# tick-mk-2.net
KiCad netlist of a schematic drawn in EAGLE
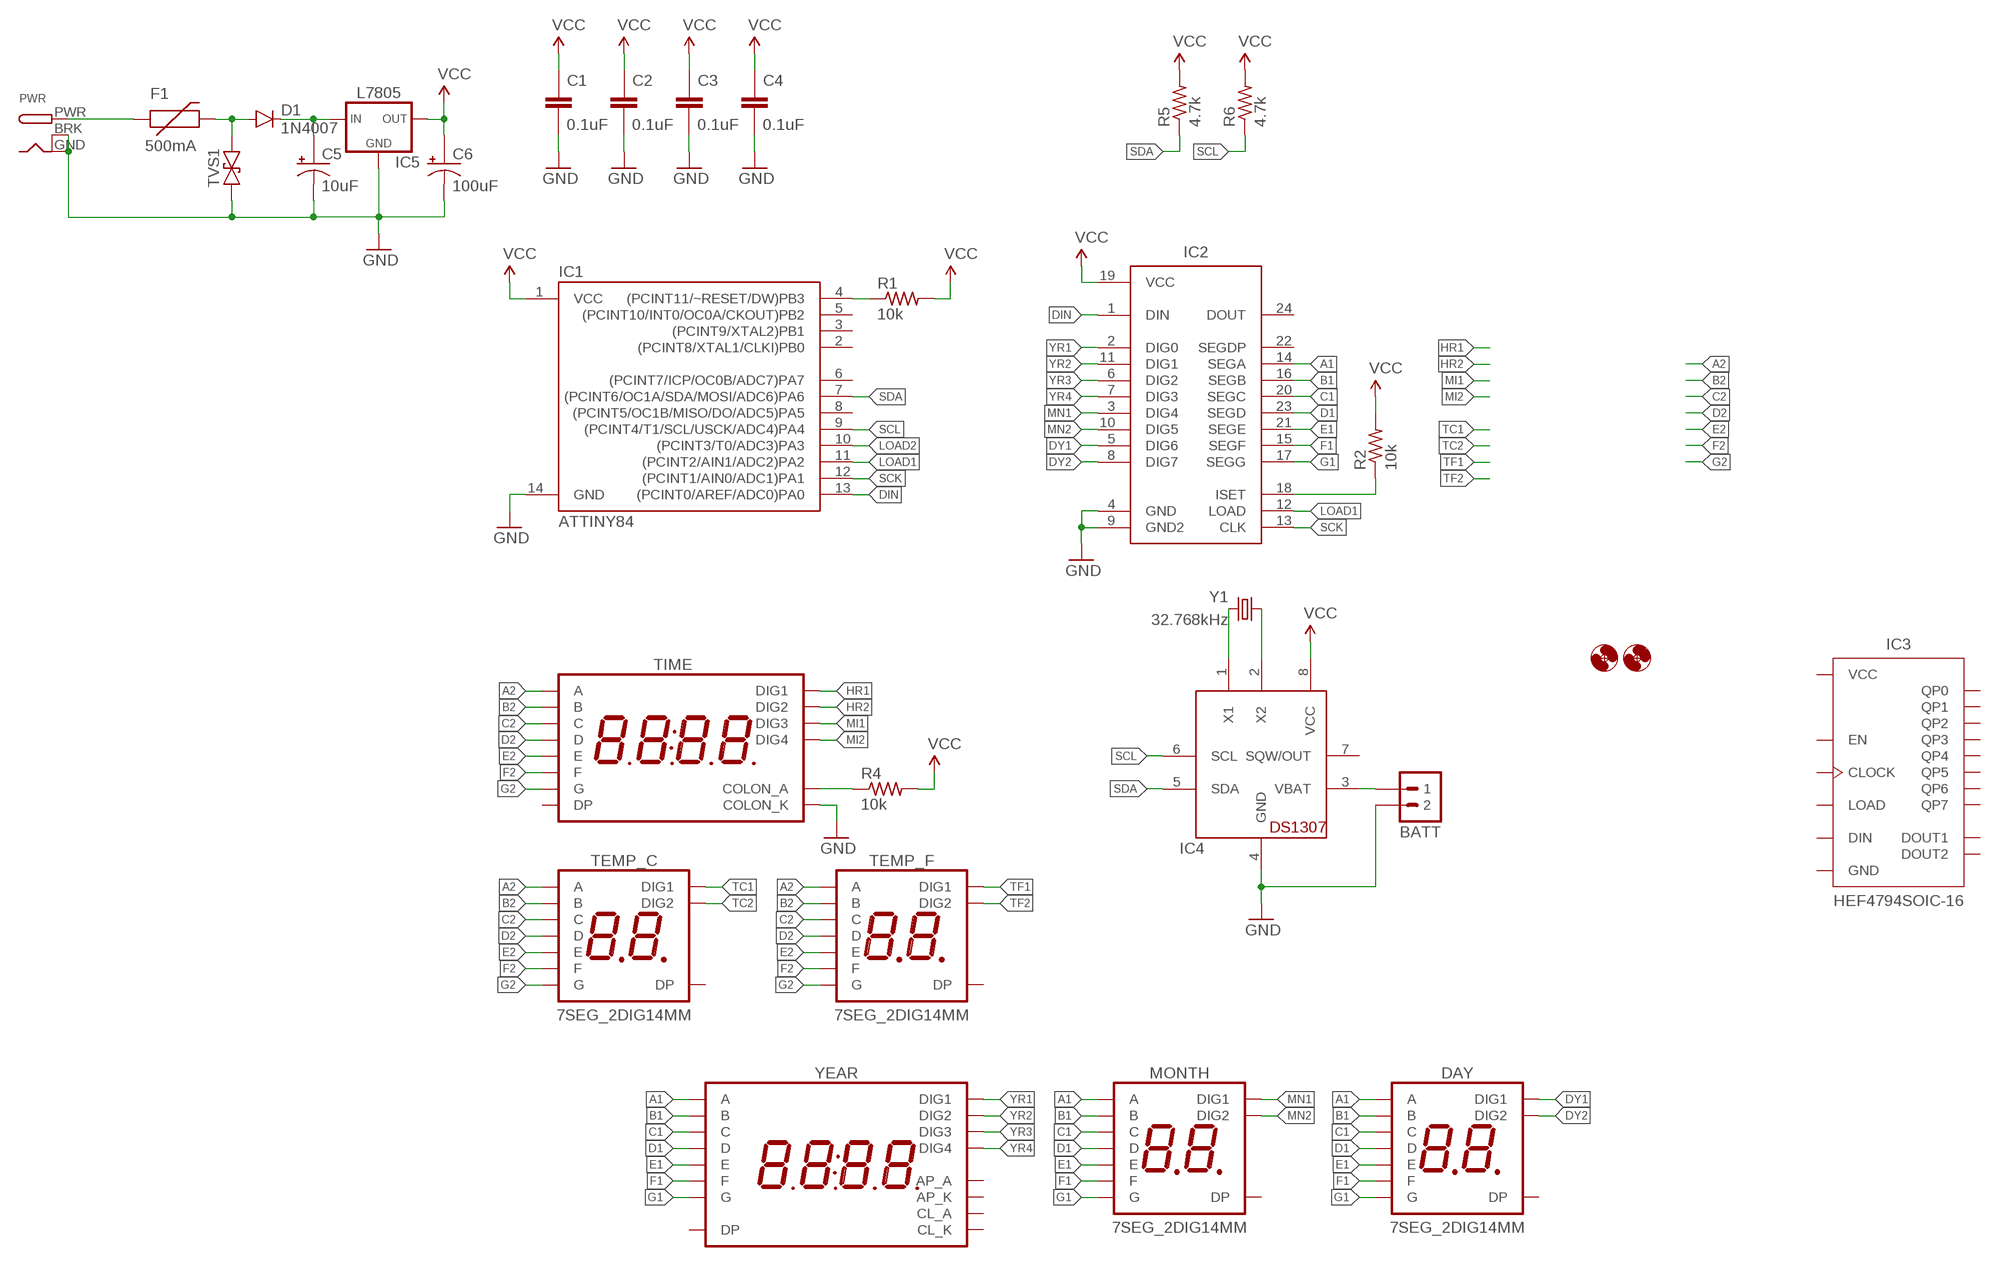
[diagram p0: schematic, sheet 1]

(export (version "E")
  (design (tool "Eeschema 10.0.6"))
  (components
    (comp (ref "BATT")
      (value "M02JST-PTH-VERT")
      (footprint "eagle-import:JST-2-PH-VERT-PTH")
      (libsource (lib "eagle-import") (part "M02JST-PTH-VERT"))
    )
    (comp (ref "C1")
      (value "0.1uF")
      (footprint "eagle-import:C025-024X044")
      (libsource (lib "eagle-import") (part "CAPACITOR-CERAMIC025-024X044"))
    )
    (comp (ref "C2")
      (value "0.1uF")
      (footprint "eagle-import:C025-024X044")
      (libsource (lib "eagle-import") (part "CAPACITOR-CERAMIC025-024X044"))
    )
    (comp (ref "C3")
      (value "0.1uF")
      (footprint "eagle-import:C025-024X044")
      (libsource (lib "eagle-import") (part "CAPACITOR-CERAMIC025-024X044"))
    )
    (comp (ref "C4")
      (value "0.1uF")
      (footprint "eagle-import:C025-024X044")
      (libsource (lib "eagle-import") (part "CAPACITOR-CERAMIC025-024X044"))
    )
    (comp (ref "C5")
      (value "10uF")
      (footprint "eagle-import:E2-5")
      (libsource (lib "eagle-import") (part "CAPACITOR-POLARIZEDE2-5"))
    )
    (comp (ref "C6")
      (value "100uF")
      (footprint "eagle-import:E2-5")
      (libsource (lib "eagle-import") (part "CAPACITOR-POLARIZEDE2-5"))
    )
    (comp (ref "D1")
      (value "1N4007")
      (footprint "eagle-import:DIODE-10.16MM")
      (libsource (lib "eagle-import") (part "DIODEPTH-10.68MM"))
    )
    (comp (ref "DAY")
      (value "7SEG_2DIG14MM")
      (footprint "eagle-import:7SEG_2DIG_14MM")
      (libsource (lib "eagle-import") (part "7SEG_2DIG14MM"))
    )
    (comp (ref "F1")
      (value "500mA")
      (footprint "eagle-import:PTC")
      (libsource (lib "eagle-import") (part "PTCPTH"))
    )
    (comp (ref "H1")
      (value "HOLE#2")
      (footprint "eagle-import:HOLE-#2")
      (libsource (lib "eagle-import") (part "HOLE#2"))
    )
    (comp (ref "H2")
      (value "HOLE#2")
      (footprint "eagle-import:HOLE-#2")
      (libsource (lib "eagle-import") (part "HOLE#2"))
    )
    (comp (ref "IC1")
      (value "ATTINY84")
      (footprint "eagle-import:DIL14")
      (libsource (lib "eagle-import") (part "ATTINY84ATTINY84-20PU"))
    )
    (comp (ref "IC2")
      (value "MAX7219")
      (footprint "eagle-import:DIL24")
      (libsource (lib "eagle-import") (part "MAX7219DIP"))
    )
    (comp (ref "IC3")
      (value "HEF4794SOIC-16")
      (footprint "eagle-import:SO16")
      (libsource (lib "eagle-import") (part "HEF4794SOIC-16"))
    )
    (comp (ref "IC4")
      (value "DS1307")
      (footprint "eagle-import:DIL08")
      (libsource (lib "eagle-import") (part "DS1307"))
    )
    (comp (ref "IC5")
      (value "L7805")
      (footprint "eagle-import:78XXL")
      (libsource (lib "eagle-import") (part "V_REG_78XXSIDE"))
    )
    (comp (ref "MONTH")
      (value "7SEG_2DIG14MM")
      (footprint "eagle-import:7SEG_2DIG_14MM")
      (libsource (lib "eagle-import") (part "7SEG_2DIG14MM"))
    )
    (comp (ref "PWR")
      (value "DCBARRELPTH")
      (footprint "eagle-import:DCJACK_2MM_PTH")
      (libsource (lib "eagle-import") (part "DCBARRELPTH"))
    )
    (comp (ref "R1")
      (value "10k")
      (footprint "eagle-import:RESISTOR-AXIAL-PTH-5.08MM")
      (libsource (lib "eagle-import") (part "RESISTORPTH-AXIAL-5.08MM"))
    )
    (comp (ref "R2")
      (value "10k")
      (footprint "eagle-import:RESISTOR-AXIAL-PTH-5.08MM")
      (libsource (lib "eagle-import") (part "RESISTORPTH-AXIAL-5.08MM"))
    )
    (comp (ref "R4")
      (value "10k")
      (footprint "eagle-import:RESISTOR-AXIAL-PTH-5.08MM")
      (libsource (lib "eagle-import") (part "RESISTORPTH-AXIAL-5.08MM"))
    )
    (comp (ref "R5")
      (value "4.7k")
      (footprint "eagle-import:RESISTOR-AXIAL-PTH-5.08MM")
      (libsource (lib "eagle-import") (part "RESISTORPTH-AXIAL-5.08MM"))
    )
    (comp (ref "R6")
      (value "4.7k")
      (footprint "eagle-import:RESISTOR-AXIAL-PTH-5.08MM")
      (libsource (lib "eagle-import") (part "RESISTORPTH-AXIAL-5.08MM"))
    )
    (comp (ref "TEMP_C")
      (value "7SEG_2DIG14MM")
      (footprint "eagle-import:7SEG_2DIG_14MM")
      (libsource (lib "eagle-import") (part "7SEG_2DIG14MM"))
    )
    (comp (ref "TEMP_F")
      (value "7SEG_2DIG14MM")
      (footprint "eagle-import:7SEG_2DIG_14MM")
      (libsource (lib "eagle-import") (part "7SEG_2DIG14MM"))
    )
    (comp (ref "TIME")
      (value "7SED_4DIGIT_14MM14.2MM-CC")
      (footprint "eagle-import:7SEG_4DIG")
      (libsource (lib "eagle-import") (part "7SED_4DIGIT_14MM14.2MM-CC"))
    )
    (comp (ref "TVS1")
      (value "TVSDO-41-TVS-BIDIRECTIONAL")
      (footprint "eagle-import:DO-41-TVS")
      (libsource (lib "eagle-import") (part "TVSDO-41-TVS-BIDIRECTIONAL"))
    )
    (comp (ref "Y1")
      (value "32.768kHz")
      (footprint "eagle-import:TC26H")
      (libsource (lib "eagle-import") (part "CRYSTALTC26H"))
    )
    (comp (ref "YEAR")
      (value "7SEG_4DIGIT_10MM")
      (footprint "eagle-import:7SEG_4DIG_10MM")
      (libsource (lib "eagle-import") (part "7SEG_4DIGIT_10MM"))
    )
  )
  (nets
    (net (code "1") (name "A1") (class "Default")
      (node (ref "DAY") (pin "4") (pinfunction "A_4") (pintype "passive"))
      (node (ref "IC2") (pin "14") (pinfunction "SEGA_14") (pintype "bidirectional"))
      (node (ref "MONTH") (pin "4") (pinfunction "A_4") (pintype "passive"))
      (node (ref "YEAR") (pin "14") (pinfunction "A_14") (pintype "passive"))
    )
    (net (code "2") (name "A2") (class "Default")
      (node (ref "TEMP_C") (pin "4") (pinfunction "A_4") (pintype "passive"))
      (node (ref "TEMP_F") (pin "4") (pinfunction "A_4") (pintype "passive"))
      (node (ref "TIME") (pin "P$13") (pinfunction "A_P$13") (pintype "passive"))
    )
    (net (code "3") (name "B1") (class "Default")
      (node (ref "DAY") (pin "3") (pinfunction "B_3") (pintype "passive"))
      (node (ref "IC2") (pin "16") (pinfunction "SEGB_16") (pintype "bidirectional"))
      (node (ref "MONTH") (pin "3") (pinfunction "B_3") (pintype "passive"))
      (node (ref "YEAR") (pin "16") (pinfunction "B_16") (pintype "passive"))
    )
    (net (code "4") (name "B2") (class "Default")
      (node (ref "TEMP_C") (pin "3") (pinfunction "B_3") (pintype "passive"))
      (node (ref "TEMP_F") (pin "3") (pinfunction "B_3") (pintype "passive"))
      (node (ref "TIME") (pin "P$9") (pinfunction "B_P$9") (pintype "passive"))
    )
    (net (code "5") (name "C1") (class "Default")
      (node (ref "DAY") (pin "9") (pinfunction "C_9") (pintype "passive"))
      (node (ref "IC2") (pin "20") (pinfunction "SEGC_20") (pintype "bidirectional"))
      (node (ref "MONTH") (pin "9") (pinfunction "C_9") (pintype "passive"))
      (node (ref "YEAR") (pin "13") (pinfunction "C_13") (pintype "passive"))
    )
    (net (code "6") (name "C2") (class "Default")
      (node (ref "TEMP_C") (pin "9") (pinfunction "C_9") (pintype "passive"))
      (node (ref "TEMP_F") (pin "9") (pinfunction "C_9") (pintype "passive"))
      (node (ref "TIME") (pin "P$4") (pinfunction "C_P$4") (pintype "passive"))
    )
    (net (code "7") (name "D1") (class "Default")
      (node (ref "DAY") (pin "8") (pinfunction "D_8") (pintype "passive"))
      (node (ref "IC2") (pin "23") (pinfunction "SEGD_23") (pintype "bidirectional"))
      (node (ref "MONTH") (pin "8") (pinfunction "D_8") (pintype "passive"))
      (node (ref "YEAR") (pin "3") (pinfunction "D_3") (pintype "passive"))
    )
    (net (code "8") (name "D2") (class "Default")
      (node (ref "TEMP_C") (pin "8") (pinfunction "D_8") (pintype "passive"))
      (node (ref "TEMP_F") (pin "8") (pinfunction "D_8") (pintype "passive"))
      (node (ref "TIME") (pin "P$2") (pinfunction "D_P$2") (pintype "passive"))
    )
    (net (code "9") (name "DIN") (class "Default")
      (node (ref "IC1") (pin "13") (pinfunction "(PCINT0/AREF/ADC0)PA0_13") (pintype "bidirectional"))
      (node (ref "IC2") (pin "1") (pinfunction "DIN_1") (pintype "bidirectional"))
    )
    (net (code "10") (name "DY1") (class "Default")
      (node (ref "DAY") (pin "5") (pinfunction "DIG1_5") (pintype "passive"))
      (node (ref "IC2") (pin "5") (pinfunction "DIG6_5") (pintype "bidirectional"))
    )
    (net (code "11") (name "DY2") (class "Default")
      (node (ref "DAY") (pin "10") (pinfunction "DIG2_10") (pintype "passive"))
      (node (ref "IC2") (pin "8") (pinfunction "DIG7_8") (pintype "bidirectional"))
    )
    (net (code "12") (name "E1") (class "Default")
      (node (ref "DAY") (pin "6") (pinfunction "E_6") (pintype "passive"))
      (node (ref "IC2") (pin "21") (pinfunction "SEGE_21") (pintype "bidirectional"))
      (node (ref "MONTH") (pin "6") (pinfunction "E_6") (pintype "passive"))
      (node (ref "YEAR") (pin "5") (pinfunction "E_5") (pintype "passive"))
    )
    (net (code "13") (name "E2") (class "Default")
      (node (ref "TEMP_C") (pin "6") (pinfunction "E_6") (pintype "passive"))
      (node (ref "TEMP_F") (pin "6") (pinfunction "E_6") (pintype "passive"))
      (node (ref "TIME") (pin "P$1") (pinfunction "E_P$1") (pintype "passive"))
    )
    (net (code "14") (name "F1") (class "Default")
      (node (ref "DAY") (pin "7") (pinfunction "F_7") (pintype "passive"))
      (node (ref "IC2") (pin "15") (pinfunction "SEGF_15") (pintype "bidirectional"))
      (node (ref "MONTH") (pin "7") (pinfunction "F_7") (pintype "passive"))
      (node (ref "YEAR") (pin "11") (pinfunction "F_11") (pintype "passive"))
    )
    (net (code "15") (name "F2") (class "Default")
      (node (ref "TEMP_C") (pin "7") (pinfunction "F_7") (pintype "passive"))
      (node (ref "TEMP_F") (pin "7") (pinfunction "F_7") (pintype "passive"))
      (node (ref "TIME") (pin "P$12") (pinfunction "F_P$12") (pintype "passive"))
    )
    (net (code "16") (name "G1") (class "Default")
      (node (ref "DAY") (pin "1") (pinfunction "G_1") (pintype "passive"))
      (node (ref "IC2") (pin "17") (pinfunction "SEGG_17") (pintype "bidirectional"))
      (node (ref "MONTH") (pin "1") (pinfunction "G_1") (pintype "passive"))
      (node (ref "YEAR") (pin "15") (pinfunction "G_15") (pintype "passive"))
    )
    (net (code "17") (name "G2") (class "Default")
      (node (ref "TEMP_C") (pin "1") (pinfunction "G_1") (pintype "passive"))
      (node (ref "TEMP_F") (pin "1") (pinfunction "G_1") (pintype "passive"))
      (node (ref "TIME") (pin "P$5") (pinfunction "G_P$5") (pintype "passive"))
    )
    (net (code "18") (name "GND") (class "Default")
      (node (ref "BATT") (pin "2") (pinfunction "2_2") (pintype "passive"))
      (node (ref "C1") (pin "2") (pinfunction "2_2") (pintype "passive"))
      (node (ref "C2") (pin "2") (pinfunction "2_2") (pintype "passive"))
      (node (ref "C3") (pin "2") (pinfunction "2_2") (pintype "passive"))
      (node (ref "C4") (pin "2") (pinfunction "2_2") (pintype "passive"))
      (node (ref "C5") (pin "-") (pinfunction "-_-") (pintype "passive"))
      (node (ref "C6") (pin "-") (pinfunction "-_-") (pintype "passive"))
      (node (ref "IC1") (pin "14") (pinfunction "GND_14") (pintype "bidirectional"))
      (node (ref "IC2") (pin "4") (pinfunction "GND_4") (pintype "bidirectional"))
      (node (ref "IC2") (pin "9") (pinfunction "GND2_9") (pintype "bidirectional"))
      (node (ref "IC4") (pin "4") (pinfunction "GND_4") (pintype "power_in"))
      (node (ref "IC5") (pin "GND") (pinfunction "GND_GND") (pintype "input"))
      (node (ref "PWR") (pin "BRK") (pinfunction "BRK_BRK") (pintype "power_in"))
      (node (ref "PWR") (pin "GND") (pinfunction "GND_GND") (pintype "power_in"))
      (node (ref "TIME") (pin "P$7") (pinfunction "COLON_K_P$7") (pintype "passive"))
      (node (ref "TVS1") (pin "P$1") (pinfunction "1_P$1") (pintype "passive"))
    )
    (net (code "19") (name "HR1") (class "Default")
      (node (ref "TIME") (pin "P$14") (pinfunction "DIG1_P$14") (pintype "passive"))
    )
    (net (code "20") (name "HR2") (class "Default")
      (node (ref "TIME") (pin "P$11") (pinfunction "DIG2_P$11") (pintype "passive"))
    )
    (net (code "21") (name "LOAD1") (class "Default")
      (node (ref "IC1") (pin "11") (pinfunction "(PCINT2/AIN1/ADC2)PA2_11") (pintype "bidirectional"))
      (node (ref "IC2") (pin "12") (pinfunction "LOAD_12") (pintype "bidirectional"))
    )
    (net (code "22") (name "LOAD2") (class "Default")
      (node (ref "IC1") (pin "10") (pinfunction "(PCINT3/T0/ADC3)PA3_10") (pintype "bidirectional"))
    )
    (net (code "23") (name "MI1") (class "Default")
      (node (ref "TIME") (pin "P$10") (pinfunction "DIG3_P$10") (pintype "passive"))
    )
    (net (code "24") (name "MI2") (class "Default")
      (node (ref "TIME") (pin "P$6") (pinfunction "DIG4_P$6") (pintype "passive"))
    )
    (net (code "25") (name "MN1") (class "Default")
      (node (ref "IC2") (pin "3") (pinfunction "DIG4_3") (pintype "bidirectional"))
      (node (ref "MONTH") (pin "5") (pinfunction "DIG1_5") (pintype "passive"))
    )
    (net (code "26") (name "MN2") (class "Default")
      (node (ref "IC2") (pin "10") (pinfunction "DIG5_10") (pintype "bidirectional"))
      (node (ref "MONTH") (pin "10") (pinfunction "DIG2_10") (pintype "passive"))
    )
    (net (code "27") (name "Net-(C5-Pad+)") (class "Default")
      (node (ref "C5") (pin "+") (pinfunction "+_+") (pintype "passive"))
      (node (ref "D1") (pin "C") (pinfunction "C_C") (pintype "passive"))
      (node (ref "IC5") (pin "IN") (pinfunction "IN_IN") (pintype "input"))
    )
    (net (code "28") (name "Net-(F1-1)") (class "Default")
      (node (ref "F1") (pin "P$1") (pinfunction "1_P$1") (pintype "bidirectional"))
      (node (ref "PWR") (pin "PWR") (pinfunction "PWR_PWR") (pintype "power_in"))
    )
    (net (code "29") (name "Net-(F1-2)") (class "Default")
      (node (ref "D1") (pin "A") (pinfunction "A_A") (pintype "passive"))
      (node (ref "F1") (pin "P$2") (pinfunction "2_P$2") (pintype "bidirectional"))
      (node (ref "TVS1") (pin "P$2") (pinfunction "2_P$2") (pintype "passive"))
    )
    (net (code "30") (name "Net-(IC1-(PCINT11{slash}~{RESET{slash}DW})PB3)") (class "Default")
      (node (ref "IC1") (pin "4") (pinfunction "(PCINT11/~{RESET/DW})PB3_4") (pintype "bidirectional"))
      (node (ref "R1") (pin "P$1") (pinfunction "1_P$1") (pintype "passive"))
    )
    (net (code "31") (name "Net-(IC2-ISET)") (class "Default")
      (node (ref "IC2") (pin "18") (pinfunction "ISET_18") (pintype "bidirectional"))
      (node (ref "R2") (pin "P$1") (pinfunction "1_P$1") (pintype "passive"))
    )
    (net (code "32") (name "Net-(IC4-VBAT)") (class "Default")
      (node (ref "BATT") (pin "1") (pinfunction "1_1") (pintype "passive"))
      (node (ref "IC4") (pin "3") (pinfunction "VBAT_3") (pintype "power_in"))
    )
    (net (code "33") (name "Net-(IC4-X1)") (class "Default")
      (node (ref "IC4") (pin "1") (pinfunction "X1_1") (pintype "passive"))
      (node (ref "Y1") (pin "2") (pinfunction "2_2") (pintype "passive"))
    )
    (net (code "34") (name "Net-(IC4-X2)") (class "Default")
      (node (ref "IC4") (pin "2") (pinfunction "X2_2") (pintype "passive"))
      (node (ref "Y1") (pin "1") (pinfunction "1_1") (pintype "passive"))
    )
    (net (code "35") (name "Net-(R4-1)") (class "Default")
      (node (ref "R4") (pin "P$1") (pinfunction "1_P$1") (pintype "passive"))
      (node (ref "TIME") (pin "P$8") (pinfunction "COLON_A_P$8") (pintype "passive"))
    )
    (net (code "36") (name "SCK") (class "Default")
      (node (ref "IC1") (pin "12") (pinfunction "(PCINT1/AIN0/ADC1)PA1_12") (pintype "bidirectional"))
      (node (ref "IC2") (pin "13") (pinfunction "CLK_13") (pintype "bidirectional"))
    )
    (net (code "37") (name "SCL") (class "Default")
      (node (ref "IC1") (pin "9") (pinfunction "(PCINT4/T1/SCL/USCK/ADC4)PA4_9") (pintype "bidirectional"))
      (node (ref "IC4") (pin "6") (pinfunction "SCL_6") (pintype "bidirectional"))
      (node (ref "R6") (pin "P$1") (pinfunction "1_P$1") (pintype "passive"))
    )
    (net (code "38") (name "SDA") (class "Default")
      (node (ref "IC1") (pin "7") (pinfunction "(PCINT6/OC1A/SDA/MOSI/ADC6)PA6_7") (pintype "bidirectional"))
      (node (ref "IC4") (pin "5") (pinfunction "SDA_5") (pintype "bidirectional"))
      (node (ref "R5") (pin "P$1") (pinfunction "1_P$1") (pintype "passive"))
    )
    (net (code "39") (name "TC1") (class "Default")
      (node (ref "TEMP_C") (pin "5") (pinfunction "DIG1_5") (pintype "passive"))
    )
    (net (code "40") (name "TC2") (class "Default")
      (node (ref "TEMP_C") (pin "10") (pinfunction "DIG2_10") (pintype "passive"))
    )
    (net (code "41") (name "TF1") (class "Default")
      (node (ref "TEMP_F") (pin "5") (pinfunction "DIG1_5") (pintype "passive"))
    )
    (net (code "42") (name "TF2") (class "Default")
      (node (ref "TEMP_F") (pin "10") (pinfunction "DIG2_10") (pintype "passive"))
    )
    (net (code "43") (name "VCC") (class "Default")
      (node (ref "C1") (pin "1") (pinfunction "1_1") (pintype "passive"))
      (node (ref "C2") (pin "1") (pinfunction "1_1") (pintype "passive"))
      (node (ref "C3") (pin "1") (pinfunction "1_1") (pintype "passive"))
      (node (ref "C4") (pin "1") (pinfunction "1_1") (pintype "passive"))
      (node (ref "C6") (pin "+") (pinfunction "+_+") (pintype "passive"))
      (node (ref "IC1") (pin "1") (pinfunction "VCC_1") (pintype "bidirectional"))
      (node (ref "IC2") (pin "19") (pinfunction "VCC_19") (pintype "bidirectional"))
      (node (ref "IC4") (pin "8") (pinfunction "VCC_8") (pintype "power_in"))
      (node (ref "IC5") (pin "OUT") (pinfunction "OUT_OUT") (pintype "output"))
      (node (ref "R1") (pin "P$2") (pinfunction "2_P$2") (pintype "passive"))
      (node (ref "R2") (pin "P$2") (pinfunction "2_P$2") (pintype "passive"))
      (node (ref "R4") (pin "P$2") (pinfunction "2_P$2") (pintype "passive"))
      (node (ref "R5") (pin "P$2") (pinfunction "2_P$2") (pintype "passive"))
      (node (ref "R6") (pin "P$2") (pinfunction "2_P$2") (pintype "passive"))
    )
    (net (code "44") (name "YR1") (class "Default")
      (node (ref "IC2") (pin "2") (pinfunction "DIG0_2") (pintype "bidirectional"))
      (node (ref "YEAR") (pin "1") (pinfunction "DIG1_1") (pintype "passive"))
    )
    (net (code "45") (name "YR2") (class "Default")
      (node (ref "IC2") (pin "11") (pinfunction "DIG1_11") (pintype "bidirectional"))
      (node (ref "YEAR") (pin "2") (pinfunction "DIG2_2") (pintype "passive"))
    )
    (net (code "46") (name "YR3") (class "Default")
      (node (ref "IC2") (pin "6") (pinfunction "DIG2_6") (pintype "bidirectional"))
      (node (ref "YEAR") (pin "6") (pinfunction "DIG3_6") (pintype "passive"))
    )
    (net (code "47") (name "YR4") (class "Default")
      (node (ref "IC2") (pin "7") (pinfunction "DIG3_7") (pintype "bidirectional"))
      (node (ref "YEAR") (pin "8") (pinfunction "DIG4_8") (pintype "passive"))
    )
    (net (code "48") (name "unconnected-(DAY-DP-Pad2)") (class "Default")
      (node (ref "DAY") (pin "2") (pinfunction "DP_2") (pintype "passive"))
    )
    (net (code "49") (name "unconnected-(IC1-(PCINT5{slash}OC1B{slash}MISO{slash}DO{slash}ADC5)PA5-Pad8)") (class "Default")
      (node (ref "IC1") (pin "8") (pinfunction "(PCINT5/OC1B/MISO/DO/ADC5)PA5_8") (pintype "bidirectional"))
    )
    (net (code "50") (name "unconnected-(IC1-(PCINT7{slash}ICP{slash}OC0B{slash}ADC7)PA7-Pad6)") (class "Default")
      (node (ref "IC1") (pin "6") (pinfunction "(PCINT7/ICP/OC0B/ADC7)PA7_6") (pintype "bidirectional"))
    )
    (net (code "51") (name "unconnected-(IC1-(PCINT8{slash}XTAL1{slash}CLKI)PB0-Pad2)") (class "Default")
      (node (ref "IC1") (pin "2") (pinfunction "(PCINT8/XTAL1/CLKI)PB0_2") (pintype "bidirectional"))
    )
    (net (code "52") (name "unconnected-(IC1-(PCINT9{slash}XTAL2)PB1-Pad3)") (class "Default")
      (node (ref "IC1") (pin "3") (pinfunction "(PCINT9/XTAL2)PB1_3") (pintype "bidirectional"))
    )
    (net (code "53") (name "unconnected-(IC1-(PCINT10{slash}INT0{slash}OC0A{slash}CKOUT)PB2-Pad5)") (class "Default")
      (node (ref "IC1") (pin "5") (pinfunction "(PCINT10/INT0/OC0A/CKOUT)PB2_5") (pintype "bidirectional"))
    )
    (net (code "54") (name "unconnected-(IC2-DOUT-Pad24)") (class "Default")
      (node (ref "IC2") (pin "24") (pinfunction "DOUT_24") (pintype "bidirectional"))
    )
    (net (code "55") (name "unconnected-(IC2-SEGDP-Pad22)") (class "Default")
      (node (ref "IC2") (pin "22") (pinfunction "SEGDP_22") (pintype "bidirectional"))
    )
    (net (code "56") (name "unconnected-(IC3-CLOCK-Pad3)") (class "Default")
      (node (ref "IC3") (pin "3") (pinfunction "CLOCK_3") (pintype "bidirectional"))
    )
    (net (code "57") (name "unconnected-(IC3-DIN-Pad2)") (class "Default")
      (node (ref "IC3") (pin "2") (pinfunction "DIN_2") (pintype "bidirectional"))
    )
    (net (code "58") (name "unconnected-(IC3-DOUT1-Pad9)") (class "Default")
      (node (ref "IC3") (pin "9") (pinfunction "DOUT1_9") (pintype "bidirectional"))
    )
    (net (code "59") (name "unconnected-(IC3-DOUT2-Pad10)") (class "Default")
      (node (ref "IC3") (pin "10") (pinfunction "DOUT2_10") (pintype "bidirectional"))
    )
    (net (code "60") (name "unconnected-(IC3-EN-Pad15)") (class "Default")
      (node (ref "IC3") (pin "15") (pinfunction "EN_15") (pintype "bidirectional"))
    )
    (net (code "61") (name "unconnected-(IC3-GND-Pad8)") (class "Default")
      (node (ref "IC3") (pin "8") (pinfunction "GND_8") (pintype "bidirectional"))
    )
    (net (code "62") (name "unconnected-(IC3-LOAD-Pad1)") (class "Default")
      (node (ref "IC3") (pin "1") (pinfunction "LOAD_1") (pintype "bidirectional"))
    )
    (net (code "63") (name "unconnected-(IC3-QP0-Pad4)") (class "Default")
      (node (ref "IC3") (pin "4") (pinfunction "QP0_4") (pintype "bidirectional"))
    )
    (net (code "64") (name "unconnected-(IC3-QP1-Pad5)") (class "Default")
      (node (ref "IC3") (pin "5") (pinfunction "QP1_5") (pintype "bidirectional"))
    )
    (net (code "65") (name "unconnected-(IC3-QP2-Pad6)") (class "Default")
      (node (ref "IC3") (pin "6") (pinfunction "QP2_6") (pintype "bidirectional"))
    )
    (net (code "66") (name "unconnected-(IC3-QP3-Pad7)") (class "Default")
      (node (ref "IC3") (pin "7") (pinfunction "QP3_7") (pintype "bidirectional"))
    )
    (net (code "67") (name "unconnected-(IC3-QP4-Pad14)") (class "Default")
      (node (ref "IC3") (pin "14") (pinfunction "QP4_14") (pintype "bidirectional"))
    )
    (net (code "68") (name "unconnected-(IC3-QP5-Pad13)") (class "Default")
      (node (ref "IC3") (pin "13") (pinfunction "QP5_13") (pintype "bidirectional"))
    )
    (net (code "69") (name "unconnected-(IC3-QP6-Pad12)") (class "Default")
      (node (ref "IC3") (pin "12") (pinfunction "QP6_12") (pintype "bidirectional"))
    )
    (net (code "70") (name "unconnected-(IC3-QP7-Pad11)") (class "Default")
      (node (ref "IC3") (pin "11") (pinfunction "QP7_11") (pintype "bidirectional"))
    )
    (net (code "71") (name "unconnected-(IC3-VCC-Pad16)") (class "Default")
      (node (ref "IC3") (pin "16") (pinfunction "VCC_16") (pintype "bidirectional"))
    )
    (net (code "72") (name "unconnected-(IC4-SQW{slash}OUT-Pad7)") (class "Default")
      (node (ref "IC4") (pin "7") (pinfunction "SQW/OUT_7") (pintype "bidirectional"))
    )
    (net (code "73") (name "unconnected-(MONTH-DP-Pad2)") (class "Default")
      (node (ref "MONTH") (pin "2") (pinfunction "DP_2") (pintype "passive"))
    )
    (net (code "74") (name "unconnected-(TEMP_C-DP-Pad2)") (class "Default")
      (node (ref "TEMP_C") (pin "2") (pinfunction "DP_2") (pintype "passive"))
    )
    (net (code "75") (name "unconnected-(TEMP_F-DP-Pad2)") (class "Default")
      (node (ref "TEMP_F") (pin "2") (pinfunction "DP_2") (pintype "passive"))
    )
    (net (code "76") (name "unconnected-(TIME-DP-PadP$3)") (class "Default")
      (node (ref "TIME") (pin "P$3") (pinfunction "DP_P$3") (pintype "passive"))
    )
    (net (code "77") (name "unconnected-(YEAR-AP_A-Pad10)") (class "Default")
      (node (ref "YEAR") (pin "10") (pinfunction "AP_A_10") (pintype "bidirectional"))
    )
    (net (code "78") (name "unconnected-(YEAR-AP_K-Pad9)") (class "Default")
      (node (ref "YEAR") (pin "9") (pinfunction "AP_K_9") (pintype "bidirectional"))
    )
    (net (code "79") (name "unconnected-(YEAR-CL_A-Pad4)") (class "Default")
      (node (ref "YEAR") (pin "4") (pinfunction "CL_A_4") (pintype "passive"))
    )
    (net (code "80") (name "unconnected-(YEAR-CL_K-Pad12)") (class "Default")
      (node (ref "YEAR") (pin "12") (pinfunction "CL_K_12") (pintype "passive"))
    )
    (net (code "81") (name "unconnected-(YEAR-DP-Pad7)") (class "Default")
      (node (ref "YEAR") (pin "7") (pinfunction "DP_7") (pintype "passive"))
    )
  )
)
